# 7segement3digits1badidea-mk-1_2.net
KiCad netlist of a schematic drawn in EAGLE
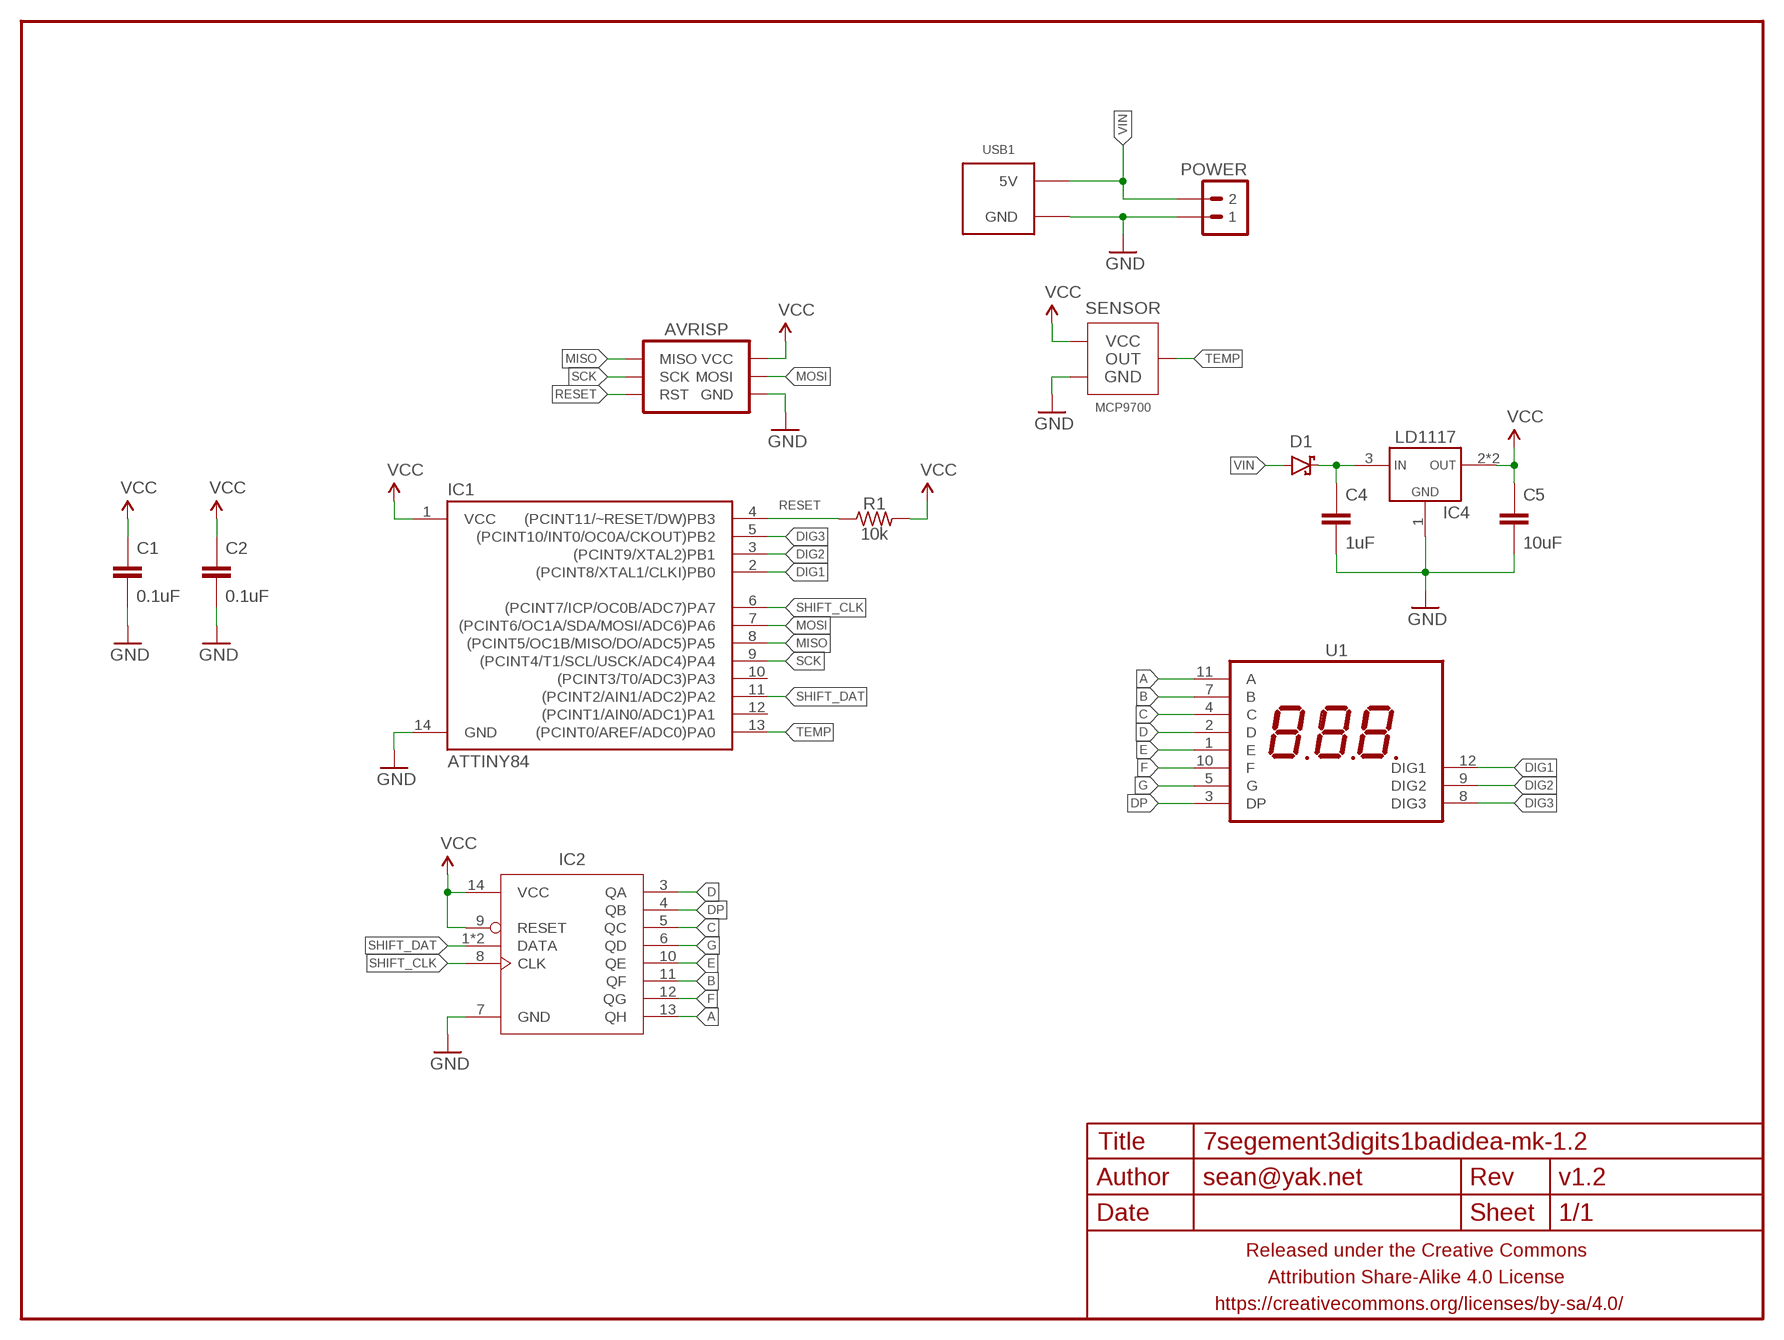
[diagram p0: schematic, sheet 1]

(export (version "E")
  (design (tool "Eeschema 10.0.6"))
  (components
    (comp (ref "AVRISP")
      (value "AVR_SPI_PRG_6TESTPOINTS")
      (footprint "eagle-import:2X3_TEST_POINTS")
      (libsource (lib "eagle-import") (part "AVR_SPI_PRG_6TESTPOINTS"))
    )
    (comp (ref "C1")
      (value "0.1uF")
      (footprint "eagle-import:C0603")
      (libsource (lib "eagle-import") (part "CAPACITOR-CERAMICC0603"))
    )
    (comp (ref "C2")
      (value "0.1uF")
      (footprint "eagle-import:C0603")
      (libsource (lib "eagle-import") (part "CAPACITOR-CERAMICC0603"))
    )
    (comp (ref "C4")
      (value "1uF")
      (footprint "eagle-import:C0805")
      (libsource (lib "eagle-import") (part "CAPACITOR-CERAMICC0805"))
    )
    (comp (ref "C5")
      (value "10uF")
      (footprint "eagle-import:C0805")
      (libsource (lib "eagle-import") (part "CAPACITOR-CERAMICC0805"))
    )
    (comp (ref "D1")
      (value "DIODE-SCHOTTKYSOD123")
      (footprint "eagle-import:SOD123-SCHOTTKY")
      (libsource (lib "eagle-import") (part "DIODE-SCHOTTKYSOD123"))
    )
    (comp (ref "FRAME1")
      (value "FRAME-LETTERNO_PACKAGE")
      (footprint "eagle-import:DUMMY")
      (fields (field (name "DESIGNER") "sean@yak.net") (field (name "VERSION") "v1.2"))
      (libsource (lib "eagle-import") (part "FRAME-LETTERNO_PACKAGE"))
    )
    (comp (ref "IC1")
      (value "ATTINY84")
      (footprint "eagle-import:SO14")
      (libsource (lib "eagle-import") (part "ATTINY84"))
    )
    (comp (ref "IC2")
      (value "74HC164")
      (footprint "eagle-import:SO14")
      (libsource (lib "eagle-import") (part "74164SOIC"))
    )
    (comp (ref "IC4")
      (value "LD1117")
      (footprint "eagle-import:SOT223")
      (libsource (lib "eagle-import") (part "VREG_1117SOT223"))
    )
    (comp (ref "POWER")
      (value "M02PTH-CENTERED-R+")
      (footprint "eagle-import:1X02-CENTER-R+")
      (libsource (lib "eagle-import") (part "M02PTH-CENTERED-R+"))
    )
    (comp (ref "R1")
      (value "10k")
      (footprint "eagle-import:R0603")
      (libsource (lib "eagle-import") (part "RESISTORR0603"))
    )
    (comp (ref "SENSOR")
      (value "MCP9700")
      (footprint "eagle-import:TO-92-AMMO")
      (libsource (lib "eagle-import") (part "MCP9700TO-92-AMMO"))
    )
    (comp (ref "U1")
      (value "7SEG_3DIGIT")
      (footprint "eagle-import:7SEG_3DIG_0.56IN")
      (libsource (lib "eagle-import") (part "7SEG_3DIGIT"))
    )
    (comp (ref "USB1")
      (value "USB_AB_PWRONLY")
      (footprint "eagle-import:FCI-10103594-USB-MICRO-B-PWRONLY")
      (libsource (lib "eagle-import") (part "USB_AB_PWRONLY"))
    )
  )
  (nets
    (net (code "1") (name "A") (class "Default")
      (node (ref "IC2") (pin "13") (pinfunction "QH_13") (pintype "bidirectional"))
      (node (ref "U1") (pin "11") (pinfunction "A_11") (pintype "passive"))
    )
    (net (code "2") (name "B") (class "Default")
      (node (ref "IC2") (pin "11") (pinfunction "QF_11") (pintype "bidirectional"))
      (node (ref "U1") (pin "7") (pinfunction "B_7") (pintype "passive"))
    )
    (net (code "3") (name "C") (class "Default")
      (node (ref "IC2") (pin "5") (pinfunction "QC_5") (pintype "bidirectional"))
      (node (ref "U1") (pin "4") (pinfunction "C_4") (pintype "passive"))
    )
    (net (code "4") (name "D") (class "Default")
      (node (ref "IC2") (pin "3") (pinfunction "QA_3") (pintype "bidirectional"))
      (node (ref "U1") (pin "2") (pinfunction "D_2") (pintype "passive"))
    )
    (net (code "5") (name "DIG1") (class "Default")
      (node (ref "IC1") (pin "2") (pinfunction "(PCINT8/XTAL1/CLKI)PB0_2") (pintype "bidirectional"))
      (node (ref "U1") (pin "12") (pinfunction "DIG1_12") (pintype "passive"))
    )
    (net (code "6") (name "DIG2") (class "Default")
      (node (ref "IC1") (pin "3") (pinfunction "(PCINT9/XTAL2)PB1_3") (pintype "bidirectional"))
      (node (ref "U1") (pin "9") (pinfunction "DIG2_9") (pintype "passive"))
    )
    (net (code "7") (name "DIG3") (class "Default")
      (node (ref "IC1") (pin "5") (pinfunction "(PCINT10/INT0/OC0A/CKOUT)PB2_5") (pintype "bidirectional"))
      (node (ref "U1") (pin "8") (pinfunction "DIG3_8") (pintype "passive"))
    )
    (net (code "8") (name "DP") (class "Default")
      (node (ref "IC2") (pin "4") (pinfunction "QB_4") (pintype "bidirectional"))
      (node (ref "U1") (pin "3") (pinfunction "DP_3") (pintype "passive"))
    )
    (net (code "9") (name "E") (class "Default")
      (node (ref "IC2") (pin "10") (pinfunction "QE_10") (pintype "bidirectional"))
      (node (ref "U1") (pin "1") (pinfunction "E_1") (pintype "passive"))
    )
    (net (code "10") (name "F") (class "Default")
      (node (ref "IC2") (pin "12") (pinfunction "QG_12") (pintype "bidirectional"))
      (node (ref "U1") (pin "10") (pinfunction "F_10") (pintype "passive"))
    )
    (net (code "11") (name "G") (class "Default")
      (node (ref "IC2") (pin "6") (pinfunction "QD_6") (pintype "bidirectional"))
      (node (ref "U1") (pin "5") (pinfunction "G_5") (pintype "passive"))
    )
    (net (code "12") (name "GND") (class "Default")
      (node (ref "AVRISP") (pin "6") (pinfunction "GND_6") (pintype "passive"))
      (node (ref "C1") (pin "2") (pinfunction "2_2") (pintype "passive"))
      (node (ref "C2") (pin "2") (pinfunction "2_2") (pintype "passive"))
      (node (ref "C4") (pin "2") (pinfunction "2_2") (pintype "passive"))
      (node (ref "C5") (pin "2") (pinfunction "2_2") (pintype "passive"))
      (node (ref "IC1") (pin "14") (pinfunction "GND_14") (pintype "bidirectional"))
      (node (ref "IC2") (pin "7") (pinfunction "GND_7") (pintype "bidirectional"))
      (node (ref "IC4") (pin "1") (pinfunction "GND_1") (pintype "bidirectional"))
      (node (ref "POWER") (pin "1") (pinfunction "1_1") (pintype "passive"))
      (node (ref "SENSOR") (pin "3") (pinfunction "GND_3") (pintype "bidirectional"))
      (node (ref "USB1") (pin "5") (pinfunction "GND_5") (pintype "bidirectional"))
      (node (ref "USB1") (pin "SHIELD@1") (pinfunction "GND_SHIELD@1") (pintype "bidirectional"))
      (node (ref "USB1") (pin "SHIELD@2") (pinfunction "GND_SHIELD@2") (pintype "bidirectional"))
      (node (ref "USB1") (pin "SHIELD@3") (pinfunction "GND_SHIELD@3") (pintype "bidirectional"))
      (node (ref "USB1") (pin "SHIELD@4") (pinfunction "GND_SHIELD@4") (pintype "bidirectional"))
    )
    (net (code "13") (name "MISO") (class "Default")
      (node (ref "AVRISP") (pin "1") (pinfunction "MISO_1") (pintype "passive"))
      (node (ref "IC1") (pin "8") (pinfunction "(PCINT5/OC1B/MISO/DO/ADC5)PA5_8") (pintype "bidirectional"))
    )
    (net (code "14") (name "MOSI") (class "Default")
      (node (ref "AVRISP") (pin "4") (pinfunction "MOSI_4") (pintype "passive"))
      (node (ref "IC1") (pin "7") (pinfunction "(PCINT6/OC1A/SDA/MOSI/ADC6)PA6_7") (pintype "bidirectional"))
    )
    (net (code "15") (name "Net-(IC4-VIN)") (class "Default")
      (node (ref "C4") (pin "1") (pinfunction "1_1") (pintype "passive"))
      (node (ref "D1") (pin "C") (pinfunction "C_C") (pintype "passive"))
      (node (ref "IC4") (pin "3") (pinfunction "VIN_3") (pintype "bidirectional"))
    )
    (net (code "16") (name "RESET") (class "Default")
      (node (ref "AVRISP") (pin "5") (pinfunction "RST_5") (pintype "passive"))
      (node (ref "IC1") (pin "4") (pinfunction "(PCINT11/~{RESET/DW})PB3_4") (pintype "bidirectional"))
      (node (ref "R1") (pin "1") (pinfunction "1_1") (pintype "passive"))
    )
    (net (code "17") (name "SCK") (class "Default")
      (node (ref "AVRISP") (pin "3") (pinfunction "SCK_3") (pintype "passive"))
      (node (ref "IC1") (pin "9") (pinfunction "(PCINT4/T1/SCL/USCK/ADC4)PA4_9") (pintype "bidirectional"))
    )
    (net (code "18") (name "SHIFT_CLK") (class "Default")
      (node (ref "IC1") (pin "6") (pinfunction "(PCINT7/ICP/OC0B/ADC7)PA7_6") (pintype "bidirectional"))
      (node (ref "IC2") (pin "8") (pinfunction "CLK_8") (pintype "bidirectional"))
    )
    (net (code "19") (name "SHIFT_DAT") (class "Default")
      (node (ref "IC1") (pin "11") (pinfunction "(PCINT2/AIN1/ADC2)PA2_11") (pintype "bidirectional"))
      (node (ref "IC2") (pin "1") (pinfunction "DATA_1") (pintype "bidirectional"))
      (node (ref "IC2") (pin "2") (pinfunction "DATA_2") (pintype "bidirectional"))
    )
    (net (code "20") (name "TEMP") (class "Default")
      (node (ref "IC1") (pin "13") (pinfunction "(PCINT0/AREF/ADC0)PA0_13") (pintype "bidirectional"))
      (node (ref "SENSOR") (pin "2") (pinfunction "OUT_2") (pintype "bidirectional"))
    )
    (net (code "21") (name "VCC") (class "Default")
      (node (ref "AVRISP") (pin "2") (pinfunction "VCC_2") (pintype "passive"))
      (node (ref "C1") (pin "1") (pinfunction "1_1") (pintype "passive"))
      (node (ref "C2") (pin "1") (pinfunction "1_1") (pintype "passive"))
      (node (ref "C5") (pin "1") (pinfunction "1_1") (pintype "passive"))
      (node (ref "IC1") (pin "1") (pinfunction "VCC_1") (pintype "bidirectional"))
      (node (ref "IC2") (pin "14") (pinfunction "VCC_14") (pintype "bidirectional"))
      (node (ref "IC2") (pin "9") (pinfunction "RESET_9") (pintype "bidirectional"))
      (node (ref "IC4") (pin "2") (pinfunction "VOUT_2") (pintype "bidirectional"))
      (node (ref "IC4") (pin "4") (pinfunction "VOUT_4") (pintype "bidirectional"))
      (node (ref "R1") (pin "2") (pinfunction "2_2") (pintype "passive"))
      (node (ref "SENSOR") (pin "1") (pinfunction "VCC_1") (pintype "bidirectional"))
    )
    (net (code "22") (name "VIN") (class "Default")
      (node (ref "D1") (pin "A") (pinfunction "A_A") (pintype "passive"))
      (node (ref "POWER") (pin "2") (pinfunction "2_2") (pintype "passive"))
      (node (ref "USB1") (pin "1") (pinfunction "5V_1") (pintype "bidirectional"))
    )
    (net (code "23") (name "unconnected-(IC1-(PCINT1{slash}AIN0{slash}ADC1)PA1-Pad12)") (class "Default")
      (node (ref "IC1") (pin "12") (pinfunction "(PCINT1/AIN0/ADC1)PA1_12") (pintype "bidirectional"))
    )
    (net (code "24") (name "unconnected-(IC1-(PCINT3{slash}T0{slash}ADC3)PA3-Pad10)") (class "Default")
      (node (ref "IC1") (pin "10") (pinfunction "(PCINT3/T0/ADC3)PA3_10") (pintype "bidirectional"))
    )
  )
)
